# v3_stim_emg.net
KiCad netlist of a schematic drawn in EAGLE
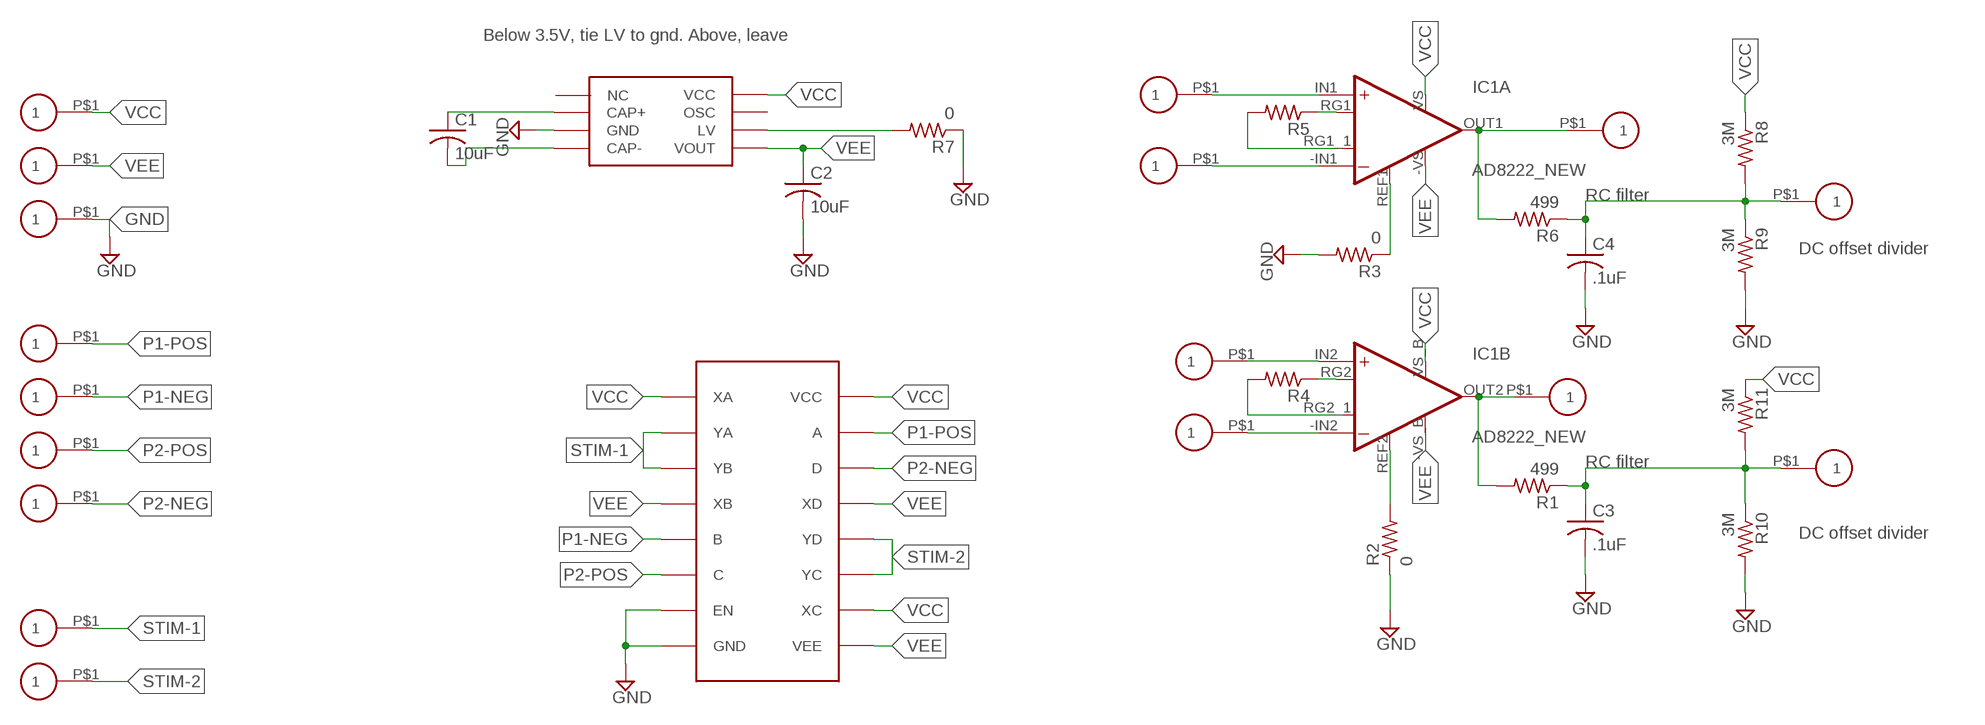
[diagram p0: schematic, sheet 1]

(export (version "E")
  (design (tool "Eeschema 10.0.6"))
  (components
    (comp (ref "A+")
      (value "DBG_ELECTRODE")
      (footprint "eagle-import:DBG_ELECTRODE")
      (libsource (lib "eagle-import") (part "DBG_ELECTRODE"))
    )
    (comp (ref "A-")
      (value "DBG_ELECTRODE")
      (footprint "eagle-import:DBG_ELECTRODE")
      (libsource (lib "eagle-import") (part "DBG_ELECTRODE"))
    )
    (comp (ref "A-OUT")
      (value "DBG_ELECTRODE")
      (footprint "eagle-import:DBG_ELECTRODE")
      (libsource (lib "eagle-import") (part "DBG_ELECTRODE"))
    )
    (comp (ref "B+")
      (value "DBG_ELECTRODE")
      (footprint "eagle-import:DBG_ELECTRODE")
      (libsource (lib "eagle-import") (part "DBG_ELECTRODE"))
    )
    (comp (ref "B-")
      (value "DBG_ELECTRODE")
      (footprint "eagle-import:DBG_ELECTRODE")
      (libsource (lib "eagle-import") (part "DBG_ELECTRODE"))
    )
    (comp (ref "B-OUT")
      (value "DBG_ELECTRODE")
      (footprint "eagle-import:DBG_ELECTRODE")
      (libsource (lib "eagle-import") (part "DBG_ELECTRODE"))
    )
    (comp (ref "C1")
      (value "10uF")
      (footprint "eagle-import:C0402")
      (libsource (lib "eagle-import") (part "C-USC0402"))
    )
    (comp (ref "C2")
      (value "10uF")
      (footprint "eagle-import:C0402")
      (libsource (lib "eagle-import") (part "C-USC0402"))
    )
    (comp (ref "C3")
      (value ".1uF")
      (footprint "eagle-import:C0402")
      (libsource (lib "eagle-import") (part "C-USC0402"))
    )
    (comp (ref "C4")
      (value ".1uF")
      (footprint "eagle-import:C0402")
      (libsource (lib "eagle-import") (part "C-USC0402"))
    )
    (comp (ref "EMG1")
      (value "DBG_ELECTRODE")
      (footprint "eagle-import:DBG_ELECTRODE")
      (libsource (lib "eagle-import") (part "DBG_ELECTRODE"))
    )
    (comp (ref "EMG2")
      (value "DBG_ELECTRODE")
      (footprint "eagle-import:DBG_ELECTRODE")
      (libsource (lib "eagle-import") (part "DBG_ELECTRODE"))
    )
    (comp (ref "GND")
      (value "DBG_ELECTRODE")
      (footprint "eagle-import:DBG_ELECTRODE")
      (libsource (lib "eagle-import") (part "DBG_ELECTRODE"))
    )
    (comp (ref "IC1")
      (value "AD8222_NEW")
      (footprint "eagle-import:QFN-16")
      (libsource (lib "eagle-import") (part "AD8222_NEW"))
    )
    (comp (ref "P1-NEG")
      (value "DBG_ELECTRODE")
      (footprint "eagle-import:DBG_ELECTRODE")
      (libsource (lib "eagle-import") (part "DBG_ELECTRODE"))
    )
    (comp (ref "P1-POS")
      (value "DBG_ELECTRODE")
      (footprint "eagle-import:DBG_ELECTRODE")
      (libsource (lib "eagle-import") (part "DBG_ELECTRODE"))
    )
    (comp (ref "P2-NEG")
      (value "DBG_ELECTRODE")
      (footprint "eagle-import:DBG_ELECTRODE")
      (libsource (lib "eagle-import") (part "DBG_ELECTRODE"))
    )
    (comp (ref "P2-POS")
      (value "DBG_ELECTRODE")
      (footprint "eagle-import:DBG_ELECTRODE")
      (libsource (lib "eagle-import") (part "DBG_ELECTRODE"))
    )
    (comp (ref "R1")
      (value "499")
      (footprint "eagle-import:R0402")
      (libsource (lib "eagle-import") (part "R-US_R0402"))
    )
    (comp (ref "R2")
      (value "0")
      (footprint "eagle-import:R0402")
      (libsource (lib "eagle-import") (part "R-US_R0402"))
    )
    (comp (ref "R3")
      (value "0")
      (footprint "eagle-import:R0402")
      (libsource (lib "eagle-import") (part "R-US_R0402"))
    )
    (comp (ref "R4")
      (value "R-US_R0402")
      (footprint "eagle-import:R0402")
      (libsource (lib "eagle-import") (part "R-US_R0402"))
    )
    (comp (ref "R5")
      (value "R-US_R0402")
      (footprint "eagle-import:R0402")
      (libsource (lib "eagle-import") (part "R-US_R0402"))
    )
    (comp (ref "R6")
      (value "499")
      (footprint "eagle-import:R0402")
      (libsource (lib "eagle-import") (part "R-US_R0402"))
    )
    (comp (ref "R7")
      (value "0")
      (footprint "eagle-import:R0402")
      (libsource (lib "eagle-import") (part "R-US_R0402"))
    )
    (comp (ref "R8")
      (value "3M")
      (footprint "eagle-import:R0402")
      (libsource (lib "eagle-import") (part "R-US_R0402"))
    )
    (comp (ref "R9")
      (value "3M")
      (footprint "eagle-import:R0402")
      (libsource (lib "eagle-import") (part "R-US_R0402"))
    )
    (comp (ref "R10")
      (value "3M")
      (footprint "eagle-import:R0402")
      (libsource (lib "eagle-import") (part "R-US_R0402"))
    )
    (comp (ref "R11")
      (value "3M")
      (footprint "eagle-import:R0402")
      (libsource (lib "eagle-import") (part "R-US_R0402"))
    )
    (comp (ref "STIM-1")
      (value "DBG_ELECTRODE")
      (footprint "eagle-import:DBG_ELECTRODE")
      (libsource (lib "eagle-import") (part "DBG_ELECTRODE"))
    )
    (comp (ref "STIM-2")
      (value "DBG_ELECTRODE")
      (footprint "eagle-import:DBG_ELECTRODE")
      (libsource (lib "eagle-import") (part "DBG_ELECTRODE"))
    )
    (comp (ref "U$1")
      (value "MC74HC4316A")
      (footprint "eagle-import:SOIC-16-ON-SEMI")
      (libsource (lib "eagle-import") (part "MC74HC4316A"))
    )
    (comp (ref "U$2")
      (value "TL7660")
      (footprint "eagle-import:S-PDSO-G8")
      (libsource (lib "eagle-import") (part "TL7660"))
    )
    (comp (ref "VCC")
      (value "DBG_ELECTRODE")
      (footprint "eagle-import:DBG_ELECTRODE")
      (libsource (lib "eagle-import") (part "DBG_ELECTRODE"))
    )
    (comp (ref "VEE")
      (value "DBG_ELECTRODE")
      (footprint "eagle-import:DBG_ELECTRODE")
      (libsource (lib "eagle-import") (part "DBG_ELECTRODE"))
    )
  )
  (nets
    (net (code "1") (name "/NC") (class "Default")
      (node (ref "U$2") (pin "1") (pinfunction "NC_1") (pintype "power_in"))
    )
    (net (code "2") (name "/OSC") (class "Default")
      (node (ref "U$2") (pin "7") (pinfunction "OSC_7") (pintype "power_in"))
    )
    (net (code "3") (name "GND") (class "Default")
      (node (ref "C2") (pin "2") (pinfunction "2_2") (pintype "passive"))
      (node (ref "C3") (pin "2") (pinfunction "2_2") (pintype "passive"))
      (node (ref "C4") (pin "2") (pinfunction "2_2") (pintype "passive"))
      (node (ref "GND") (pin "P$1") (pinfunction "1_P$1") (pintype "bidirectional"))
      (node (ref "R10") (pin "2") (pinfunction "2_2") (pintype "passive"))
      (node (ref "R2") (pin "1") (pinfunction "1_1") (pintype "passive"))
      (node (ref "R3") (pin "2") (pinfunction "2_2") (pintype "passive"))
      (node (ref "R7") (pin "1") (pinfunction "1_1") (pintype "passive"))
      (node (ref "R9") (pin "2") (pinfunction "2_2") (pintype "passive"))
      (node (ref "U$1") (pin "7") (pinfunction "EN_7") (pintype "input"))
      (node (ref "U$1") (pin "8") (pinfunction "GND_8") (pintype "power_in"))
      (node (ref "U$2") (pin "3") (pinfunction "GND_3") (pintype "power_in"))
    )
    (net (code "4") (name "Net-(A+-1)") (class "Default")
      (node (ref "A+") (pin "P$1") (pinfunction "1_P$1") (pintype "bidirectional"))
      (node (ref "IC1") (pin "IN1") (pinfunction "+IN_IN1") (pintype "input"))
    )
    (net (code "5") (name "Net-(A--1)") (class "Default")
      (node (ref "A-") (pin "P$1") (pinfunction "1_P$1") (pintype "bidirectional"))
      (node (ref "IC1") (pin "-IN1") (pinfunction "-IN_-IN1") (pintype "input"))
    )
    (net (code "6") (name "Net-(A-OUT-1)") (class "Default")
      (node (ref "A-OUT") (pin "P$1") (pinfunction "1_P$1") (pintype "bidirectional"))
      (node (ref "IC1") (pin "OUT1") (pinfunction "OUT_OUT1") (pintype "input"))
      (node (ref "R6") (pin "2") (pinfunction "2_2") (pintype "passive"))
    )
    (net (code "7") (name "Net-(B+-1)") (class "Default")
      (node (ref "B+") (pin "P$1") (pinfunction "1_P$1") (pintype "bidirectional"))
      (node (ref "IC1") (pin "IN2") (pinfunction "+IN_IN2") (pintype "input"))
    )
    (net (code "8") (name "Net-(B--1)") (class "Default")
      (node (ref "B-") (pin "P$1") (pinfunction "1_P$1") (pintype "bidirectional"))
      (node (ref "IC1") (pin "-IN2") (pinfunction "-IN_-IN2") (pintype "input"))
    )
    (net (code "9") (name "Net-(B-OUT-1)") (class "Default")
      (node (ref "B-OUT") (pin "P$1") (pinfunction "1_P$1") (pintype "bidirectional"))
      (node (ref "IC1") (pin "OUT2") (pinfunction "OUT_OUT2") (pintype "input"))
      (node (ref "R1") (pin "2") (pinfunction "2_2") (pintype "passive"))
    )
    (net (code "10") (name "Net-(EMG1-1)") (class "Default")
      (node (ref "C4") (pin "1") (pinfunction "1_1") (pintype "passive"))
      (node (ref "EMG1") (pin "P$1") (pinfunction "1_P$1") (pintype "bidirectional"))
      (node (ref "R6") (pin "1") (pinfunction "1_1") (pintype "passive"))
      (node (ref "R8") (pin "2") (pinfunction "2_2") (pintype "passive"))
      (node (ref "R9") (pin "1") (pinfunction "1_1") (pintype "passive"))
    )
    (net (code "11") (name "Net-(EMG2-1)") (class "Default")
      (node (ref "C3") (pin "1") (pinfunction "1_1") (pintype "passive"))
      (node (ref "EMG2") (pin "P$1") (pinfunction "1_P$1") (pintype "bidirectional"))
      (node (ref "R1") (pin "1") (pinfunction "1_1") (pintype "passive"))
      (node (ref "R10") (pin "1") (pinfunction "1_1") (pintype "passive"))
      (node (ref "R11") (pin "2") (pinfunction "2_2") (pintype "passive"))
    )
    (net (code "12") (name "Net-(IC1-PadRG1)") (class "Default")
      (node (ref "IC1") (pin "RG1") (pinfunction "RG1_RG1") (pintype "input"))
      (node (ref "R5") (pin "1") (pinfunction "1_1") (pintype "passive"))
    )
    (net (code "13") (name "Net-(IC1-PadRG1_1)") (class "Default")
      (node (ref "IC1") (pin "RG1_1") (pinfunction "RG1_1_RG1_1") (pintype "input"))
      (node (ref "R5") (pin "2") (pinfunction "2_2") (pintype "passive"))
    )
    (net (code "14") (name "Net-(IC1A-REF)") (class "Default")
      (node (ref "IC1") (pin "REF1") (pinfunction "REF_REF1") (pintype "input"))
      (node (ref "R3") (pin "1") (pinfunction "1_1") (pintype "passive"))
    )
    (net (code "15") (name "Net-(IC1B-REF)") (class "Default")
      (node (ref "IC1") (pin "REF2") (pinfunction "REF_REF2") (pintype "input"))
      (node (ref "R2") (pin "2") (pinfunction "2_2") (pintype "passive"))
    )
    (net (code "16") (name "Net-(IC1B-RG1)") (class "Default")
      (node (ref "IC1") (pin "RG2") (pinfunction "RG1_RG2") (pintype "input"))
      (node (ref "R4") (pin "1") (pinfunction "1_1") (pintype "passive"))
    )
    (net (code "17") (name "Net-(IC1B-RG1_1)") (class "Default")
      (node (ref "IC1") (pin "RG2_1") (pinfunction "RG1_1_RG2_1") (pintype "input"))
      (node (ref "R4") (pin "2") (pinfunction "2_2") (pintype "passive"))
    )
    (net (code "18") (name "Net-(U$2-CAP+)") (class "Default")
      (node (ref "C1") (pin "1") (pinfunction "1_1") (pintype "passive"))
      (node (ref "U$2") (pin "2") (pinfunction "CAP+_2") (pintype "power_in"))
    )
    (net (code "19") (name "Net-(U$2-CAP-)") (class "Default")
      (node (ref "C1") (pin "2") (pinfunction "2_2") (pintype "passive"))
      (node (ref "U$2") (pin "4") (pinfunction "CAP-_4") (pintype "power_in"))
    )
    (net (code "20") (name "Net-(U$2-LV)") (class "Default")
      (node (ref "R7") (pin "2") (pinfunction "2_2") (pintype "passive"))
      (node (ref "U$2") (pin "6") (pinfunction "LV_6") (pintype "power_in"))
    )
    (net (code "21") (name "P1-NEG") (class "Default")
      (node (ref "P1-NEG") (pin "P$1") (pinfunction "1_P$1") (pintype "bidirectional"))
      (node (ref "U$1") (pin "5") (pinfunction "B_5") (pintype "input"))
    )
    (net (code "22") (name "P1-POS") (class "Default")
      (node (ref "P1-POS") (pin "P$1") (pinfunction "1_P$1") (pintype "bidirectional"))
      (node (ref "U$1") (pin "15") (pinfunction "A_15") (pintype "input"))
    )
    (net (code "23") (name "P2-NEG") (class "Default")
      (node (ref "P2-NEG") (pin "P$1") (pinfunction "1_P$1") (pintype "bidirectional"))
      (node (ref "U$1") (pin "14") (pinfunction "D_14") (pintype "input"))
    )
    (net (code "24") (name "P2-POS") (class "Default")
      (node (ref "P2-POS") (pin "P$1") (pinfunction "1_P$1") (pintype "bidirectional"))
      (node (ref "U$1") (pin "6") (pinfunction "C_6") (pintype "input"))
    )
    (net (code "25") (name "STIM-1") (class "Default")
      (node (ref "STIM-1") (pin "P$1") (pinfunction "1_P$1") (pintype "bidirectional"))
      (node (ref "U$1") (pin "2") (pinfunction "YA_2") (pintype "output"))
      (node (ref "U$1") (pin "3") (pinfunction "YB_3") (pintype "output"))
    )
    (net (code "26") (name "STIM-2") (class "Default")
      (node (ref "STIM-2") (pin "P$1") (pinfunction "1_P$1") (pintype "bidirectional"))
      (node (ref "U$1") (pin "11") (pinfunction "YC_11") (pintype "output"))
      (node (ref "U$1") (pin "12") (pinfunction "YD_12") (pintype "output"))
    )
    (net (code "27") (name "VCC") (class "Default")
      (node (ref "IC1") (pin "VS") (pinfunction "V+_VS") (pintype "power_in"))
      (node (ref "IC1") (pin "VS_B") (pinfunction "V+_VS_B") (pintype "power_in"))
      (node (ref "R11") (pin "1") (pinfunction "1_1") (pintype "passive"))
      (node (ref "R8") (pin "1") (pinfunction "1_1") (pintype "passive"))
      (node (ref "U$1") (pin "1") (pinfunction "XA_1") (pintype "input"))
      (node (ref "U$1") (pin "10") (pinfunction "XC_10") (pintype "input"))
      (node (ref "U$1") (pin "16") (pinfunction "VCC_16") (pintype "power_in"))
      (node (ref "U$2") (pin "8") (pinfunction "VCC_8") (pintype "power_in"))
      (node (ref "VCC") (pin "P$1") (pinfunction "1_P$1") (pintype "bidirectional"))
    )
    (net (code "28") (name "VEE") (class "Default")
      (node (ref "C2") (pin "1") (pinfunction "1_1") (pintype "passive"))
      (node (ref "IC1") (pin "-VS") (pinfunction "V-_-VS") (pintype "power_in"))
      (node (ref "IC1") (pin "-VS_B") (pinfunction "V-_-VS_B") (pintype "power_in"))
      (node (ref "U$1") (pin "13") (pinfunction "XD_13") (pintype "input"))
      (node (ref "U$1") (pin "4") (pinfunction "XB_4") (pintype "input"))
      (node (ref "U$1") (pin "9") (pinfunction "VEE_9") (pintype "power_in"))
      (node (ref "U$2") (pin "5") (pinfunction "VOUT_5") (pintype "power_in"))
      (node (ref "VEE") (pin "P$1") (pinfunction "1_P$1") (pintype "bidirectional"))
    )
  )
)
